# Controller.net
KiCad netlist of a schematic drawn in Altium Designer
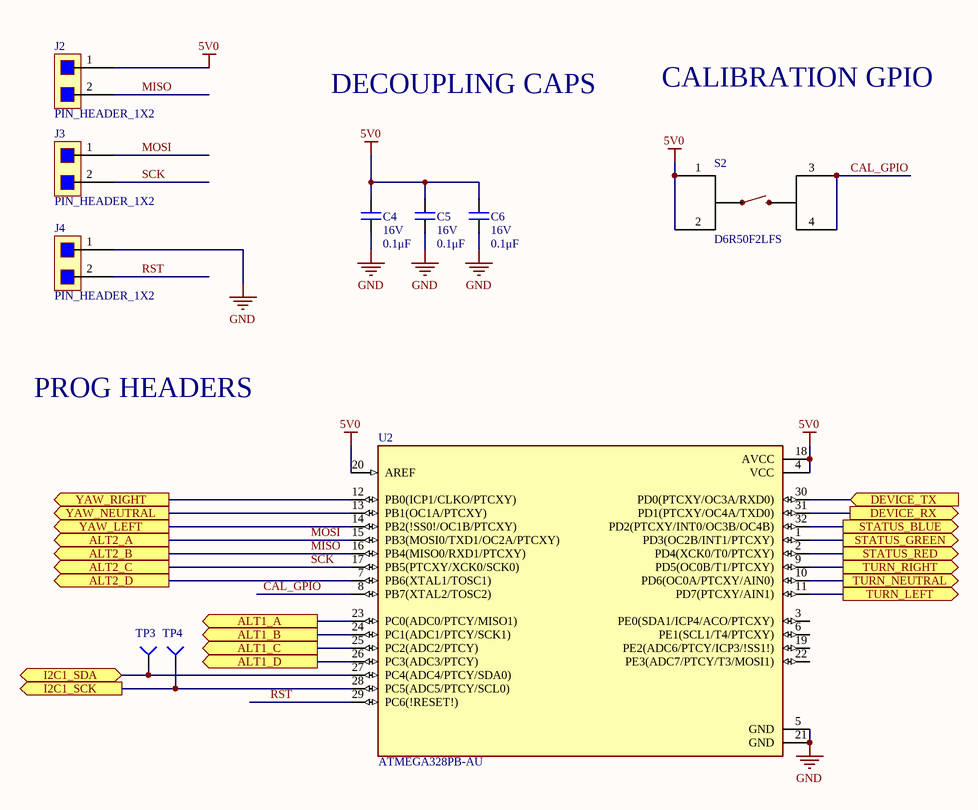
[diagram p0: Controller.SchDoc]

(export (version "E")
  (design (tool "Eeschema 10.0.6"))
  (components
    (comp (ref "C4")
      (value "0.1μF")
      (footprint "CAP0603")
      (description "CAP CER 0.1UF 16V X7R 0603")
      (fields (field (name "VOLTAGE RATING") "16V") (field (name "Comment") "CAP_0.1uF_16V_0603"))
      (libsource (lib "SKALE_LIB") (part "CAP_0.1uF_16V_0603"))
    )
    (comp (ref "C5")
      (value "0.1μF")
      (footprint "CAP0603")
      (description "CAP CER 0.1UF 16V X7R 0603")
      (fields (field (name "VOLTAGE RATING") "16V") (field (name "Comment") "CAP_0.1uF_16V_0603"))
      (libsource (lib "SKALE_LIB") (part "CAP_0.1uF_16V_0603"))
    )
    (comp (ref "C6")
      (value "0.1μF")
      (footprint "CAP0603")
      (description "CAP CER 0.1UF 16V X7R 0603")
      (fields (field (name "VOLTAGE RATING") "16V") (field (name "Comment") "CAP_0.1uF_16V_0603"))
      (libsource (lib "SKALE_LIB") (part "CAP_0.1uF_16V_0603"))
    )
    (comp (ref "J2")
      (value "PIN_HEADER_1X2")
      (footprint "PIN_HEADER - 1X2")
      (description "Board Connector, 1 Contact(s), 1 Row(s), Male, Straight, Solder Terminal")
      (fields
        (field (name "MANUFACTURER") "Sullins")
        (field (name "MANUFACTURER PART NUMBER") "PREC001SAAN-RC")
      )
      (libsource (lib "SKALE_LIB") (part "PIN_HEADER_1X2"))
    )
    (comp (ref "J3")
      (value "PIN_HEADER_1X2")
      (footprint "PIN_HEADER - 1X2")
      (description "Board Connector, 1 Contact(s), 1 Row(s), Male, Straight, Solder Terminal")
      (fields
        (field (name "MANUFACTURER") "Sullins")
        (field (name "MANUFACTURER PART NUMBER") "PREC001SAAN-RC")
      )
      (libsource (lib "SKALE_LIB") (part "PIN_HEADER_1X2"))
    )
    (comp (ref "J4")
      (value "PIN_HEADER_1X2")
      (footprint "PIN_HEADER - 1X2")
      (description "Board Connector, 1 Contact(s), 1 Row(s), Male, Straight, Solder Terminal")
      (fields
        (field (name "MANUFACTURER") "Sullins")
        (field (name "MANUFACTURER PART NUMBER") "PREC001SAAN-RC")
      )
      (libsource (lib "SKALE_LIB") (part "PIN_HEADER_1X2"))
    )
    (comp (ref "S2")
      (value "SW_MOMENTARY_SPST")
      (footprint "D6R")
      (description "SWITCH PUSH SPST-NO 0.1A 32V")
      (fields (field (name "MANUFACTURER PART NUMBER 1") "D6R50F2LFS"))
      (libsource (lib "SKALE_LIB") (part "SW_MOMENTARY_SPST"))
    )
    (comp (ref "TP3")
      (value "TESTPT")
      (footprint "TESTPT SQUARE")
      (libsource (lib "SKALE_LIB") (part "TESTPT SQUARE"))
    )
    (comp (ref "TP4")
      (value "TESTPT")
      (footprint "TESTPT SQUARE")
      (libsource (lib "SKALE_LIB") (part "TESTPT SQUARE"))
    )
    (comp (ref "U2")
      (value "ATMEGA328PB-AU")
      (footprint "QFP80P900X900X120-32N")
      (description "RISC Microcontroller, 8-Bit, FLASH, AVR RISC CPU, 20MHz, CMOS, PQFP32")
      (fields
        (field (name "MF") "Microchip Technology")
        (field (name "DIGI-KEY_PART_NUMBER") "ATMEGA328PB-AU-ND")
      )
      (libsource (lib "SKALE_LIB") (part "ATMEGA328PB-AU"))
    )
  )
  (nets
    (net (code "1") (name "/ALT1_A") (class "Default")
      (node (ref "U2") (pin "23") (pinfunction "PC0(ADC0/PTCY/MISO1)_23") (pintype "bidirectional"))
    )
    (net (code "2") (name "/ALT1_B") (class "Default")
      (node (ref "U2") (pin "24") (pinfunction "PC1(ADC1/PTCY/SCK1)_24") (pintype "bidirectional"))
    )
    (net (code "3") (name "/ALT1_C") (class "Default")
      (node (ref "U2") (pin "25") (pinfunction "PC2(ADC2/PTCY)_25") (pintype "bidirectional"))
    )
    (net (code "4") (name "/ALT1_D") (class "Default")
      (node (ref "U2") (pin "26") (pinfunction "PC3(ADC3/PTCY)_26") (pintype "bidirectional"))
    )
    (net (code "5") (name "/ALT2_D") (class "Default")
      (node (ref "U2") (pin "7") (pinfunction "PB6(XTAL1/TOSC1)_7") (pintype "bidirectional"))
    )
    (net (code "6") (name "/CAL_GPIO") (class "Default")
      (node (ref "S2") (pin "3") (pinfunction "3_3") (pintype "passive"))
      (node (ref "S2") (pin "4") (pinfunction "4_4") (pintype "passive"))
      (node (ref "U2") (pin "8") (pinfunction "PB7(XTAL2/TOSC2)_8") (pintype "bidirectional"))
    )
    (net (code "7") (name "/DEVICE_RX") (class "Default")
      (node (ref "U2") (pin "31") (pinfunction "PD1(PTCXY/OC4A/TXD0)_31") (pintype "bidirectional"))
    )
    (net (code "8") (name "/DEVICE_TX") (class "Default")
      (node (ref "U2") (pin "30") (pinfunction "PD0(PTCXY/OC3A/RXD0)_30") (pintype "bidirectional"))
    )
    (net (code "9") (name "/I2C1_SCK") (class "Default")
      (node (ref "TP4") (pin "1") (pinfunction "=value_1") (pintype "passive"))
      (node (ref "U2") (pin "28") (pinfunction "PC5(ADC5/PTCY/SCL0)_28") (pintype "bidirectional"))
    )
    (net (code "10") (name "/I2C1_SDA") (class "Default")
      (node (ref "TP3") (pin "1") (pinfunction "=value_1") (pintype "passive"))
      (node (ref "U2") (pin "27") (pinfunction "PC4(ADC4/PTCY/SDA0)_27") (pintype "bidirectional"))
    )
    (net (code "11") (name "/MISO") (class "Default")
      (node (ref "J2") (pin "2") (pinfunction "0_2") (pintype "passive"))
      (node (ref "U2") (pin "16") (pinfunction "PB4(MISO0/RXD1/PTCXY)_16") (pintype "bidirectional"))
    )
    (net (code "12") (name "/MOSI") (class "Default")
      (node (ref "J3") (pin "1") (pinfunction "0_1") (pintype "passive"))
      (node (ref "U2") (pin "15") (pinfunction "PB3(MOSI0/TXD1/OC2A/PTCXY)_15") (pintype "bidirectional"))
    )
    (net (code "13") (name "/RST") (class "Default")
      (node (ref "J4") (pin "2") (pinfunction "0_2") (pintype "passive"))
      (node (ref "U2") (pin "29") (pinfunction "PC6(!RESET!)_29") (pintype "bidirectional"))
    )
    (net (code "14") (name "/SCK") (class "Default")
      (node (ref "J3") (pin "2") (pinfunction "0_2") (pintype "passive"))
      (node (ref "U2") (pin "17") (pinfunction "PB5(PTCXY/XCK0/SCK0)_17") (pintype "bidirectional"))
    )
    (net (code "15") (name "/STATUS_BLUE") (class "Default")
      (node (ref "U2") (pin "32") (pinfunction "PD2(PTCXY/INT0/OC3B/OC4B)_32") (pintype "bidirectional"))
    )
    (net (code "16") (name "/STATUS_GREEN") (class "Default")
      (node (ref "U2") (pin "1") (pinfunction "PD3(OC2B/INT1/PTCXY)_1") (pintype "bidirectional"))
    )
    (net (code "17") (name "/STATUS_RED") (class "Default")
      (node (ref "U2") (pin "2") (pinfunction "PD4(XCK0/T0/PTCXY)_2") (pintype "bidirectional"))
    )
    (net (code "18") (name "/TURN_LEFT") (class "Default")
      (node (ref "U2") (pin "11") (pinfunction "PD7(PTCXY/AIN1)_11") (pintype "bidirectional"))
    )
    (net (code "19") (name "/TURN_NEUTRAL") (class "Default")
      (node (ref "U2") (pin "10") (pinfunction "PD6(OC0A/PTCXY/AIN0)_10") (pintype "bidirectional"))
    )
    (net (code "20") (name "/TURN_RIGHT") (class "Default")
      (node (ref "U2") (pin "9") (pinfunction "PD5(OC0B/T1/PTCXY)_9") (pintype "bidirectional"))
    )
    (net (code "21") (name "/YAW_LEFT") (class "Default")
      (node (ref "U2") (pin "14") (pinfunction "PB2(!SS0!/OC1B/PTCXY)_14") (pintype "bidirectional"))
    )
    (net (code "22") (name "/YAW_NEUTRAL") (class "Default")
      (node (ref "U2") (pin "13") (pinfunction "PB1(OC1A/PTCXY)_13") (pintype "bidirectional"))
    )
    (net (code "23") (name "/YAW_RIGHT") (class "Default")
      (node (ref "U2") (pin "12") (pinfunction "PB0(ICP1/CLKO/PTCXY)_12") (pintype "bidirectional"))
    )
    (net (code "24") (name "5V0") (class "Default")
      (node (ref "C4") (pin "2") (pinfunction "2_2") (pintype "passive"))
      (node (ref "C5") (pin "2") (pinfunction "2_2") (pintype "passive"))
      (node (ref "C6") (pin "2") (pinfunction "2_2") (pintype "passive"))
      (node (ref "J2") (pin "1") (pinfunction "0_1") (pintype "passive"))
      (node (ref "S2") (pin "1") (pinfunction "1_1") (pintype "passive"))
      (node (ref "S2") (pin "2") (pinfunction "2_2") (pintype "passive"))
      (node (ref "U2") (pin "18") (pinfunction "AVCC_18") (pintype "power_in"))
      (node (ref "U2") (pin "20") (pinfunction "AREF_20") (pintype "input"))
      (node (ref "U2") (pin "4") (pinfunction "VCC_4") (pintype "power_in"))
    )
    (net (code "25") (name "GND") (class "Default")
      (node (ref "C4") (pin "1") (pinfunction "1_1") (pintype "passive"))
      (node (ref "C5") (pin "1") (pinfunction "1_1") (pintype "passive"))
      (node (ref "C6") (pin "1") (pinfunction "1_1") (pintype "passive"))
      (node (ref "J4") (pin "1") (pinfunction "0_1") (pintype "passive"))
      (node (ref "U2") (pin "21") (pinfunction "GND_21") (pintype "power_in"))
      (node (ref "U2") (pin "5") (pinfunction "GND_5") (pintype "power_in"))
    )
    (net (code "26") (name "unconnected-(U2-PE0(SDA1{slash}ICP4{slash}ACO{slash}PTCXY)-Pad3)") (class "Default")
      (node (ref "U2") (pin "3") (pinfunction "PE0(SDA1/ICP4/ACO/PTCXY)_3") (pintype "bidirectional"))
    )
    (net (code "27") (name "unconnected-(U2-PE1(SCL1{slash}T4{slash}PTCXY)-Pad6)") (class "Default")
      (node (ref "U2") (pin "6") (pinfunction "PE1(SCL1/T4/PTCXY)_6") (pintype "bidirectional"))
    )
    (net (code "28") (name "unconnected-(U2-PE2(ADC6{slash}PTCY{slash}ICP3{slash}!SS1!)-Pad19)") (class "Default")
      (node (ref "U2") (pin "19") (pinfunction "PE2(ADC6/PTCY/ICP3/!SS1!)_19") (pintype "bidirectional"))
    )
    (net (code "29") (name "unconnected-(U2-PE3(ADC7{slash}PTCY{slash}T3{slash}MOSI1)-Pad22)") (class "Default")
      (node (ref "U2") (pin "22") (pinfunction "PE3(ADC7/PTCY/T3/MOSI1)_22") (pintype "bidirectional"))
    )
  )
)
